# CLK_16GHz.net
KiCad netlist of a schematic drawn in Altium Designer
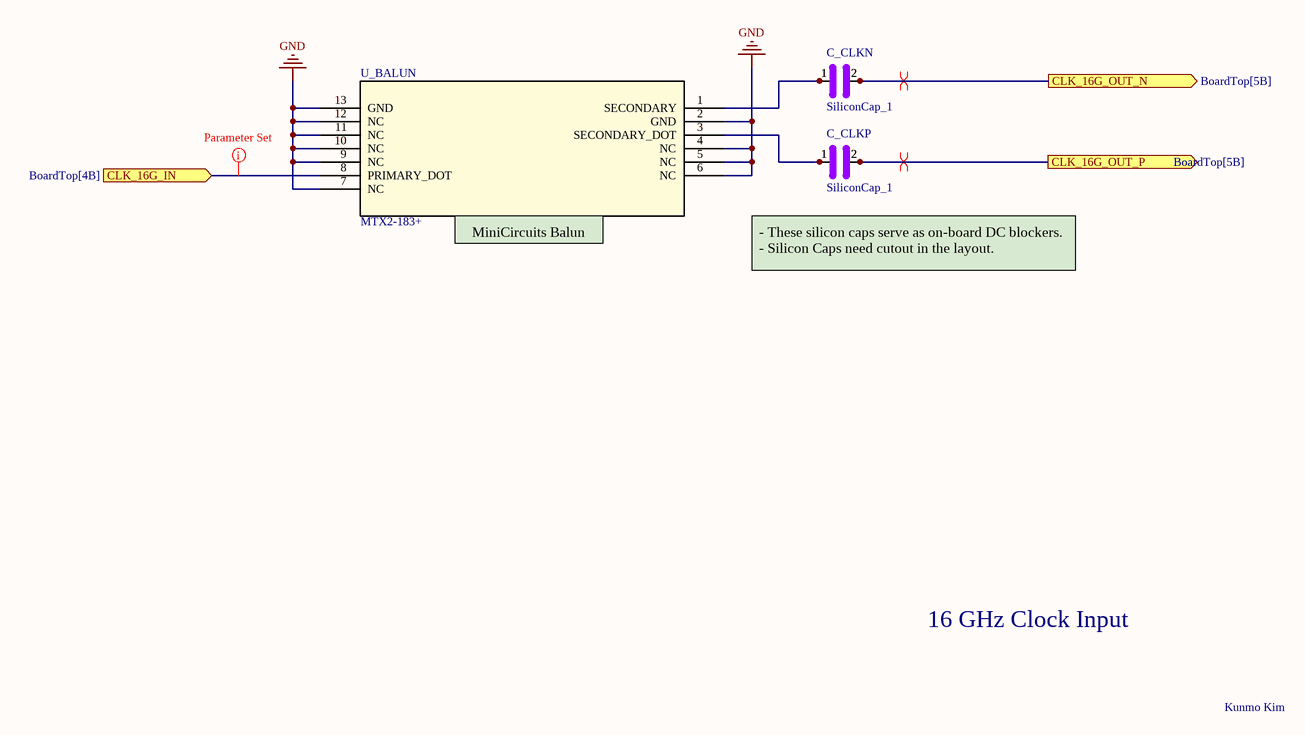
[diagram p0: CLK_16GHz.SchDoc]

(export (version "E")
  (design (tool "Eeschema 10.0.6"))
  (components
    (comp (ref "C_CLKN")
      (value "SiliconCap_1")
      (footprint "0201-NOSILK")
      (description "939114492510-T3S from Murata")
      (libsource (lib "DC_Blocker") (part "SiliconCap_1"))
    )
    (comp (ref "C_CLKP")
      (value "SiliconCap_1")
      (footprint "0201-NOSILK")
      (description "939114492510-T3S from Murata")
      (libsource (lib "DC_Blocker") (part "SiliconCap_1"))
    )
    (comp (ref "U_BALUN")
      (value "MTX2-183+")
      (footprint "DG3006_MNC")
      (libsource (lib "MTX2-133&plus_") (part "MTX2-133+"))
    )
  )
  (nets
    (net (code "1") (name "/CLK_16G_IN") (class "Default")
      (node (ref "U_BALUN") (pin "8") (pinfunction "PRIMARY_DOT_8") (pintype "passive"))
    )
    (net (code "2") (name "/CLK_16G_OUT_N") (class "Default")
      (node (ref "C_CLKN") (pin "2") (pinfunction "2_2") (pintype "passive"))
    )
    (net (code "3") (name "/CLK_16G_OUT_P") (class "Default")
      (node (ref "C_CLKP") (pin "2") (pinfunction "2_2") (pintype "passive"))
    )
    (net (code "4") (name "GND") (class "Default")
      (node (ref "U_BALUN") (pin "10") (pinfunction "NC_10") (pintype "passive"))
      (node (ref "U_BALUN") (pin "11") (pinfunction "NC_11") (pintype "passive"))
      (node (ref "U_BALUN") (pin "12") (pinfunction "NC_12") (pintype "passive"))
      (node (ref "U_BALUN") (pin "13") (pinfunction "GND_13") (pintype "power_in"))
      (node (ref "U_BALUN") (pin "2") (pinfunction "GND_2") (pintype "power_in"))
      (node (ref "U_BALUN") (pin "4") (pinfunction "NC_4") (pintype "passive"))
      (node (ref "U_BALUN") (pin "5") (pinfunction "NC_5") (pintype "passive"))
      (node (ref "U_BALUN") (pin "6") (pinfunction "NC_6") (pintype "passive"))
      (node (ref "U_BALUN") (pin "7") (pinfunction "NC_7") (pintype "passive"))
      (node (ref "U_BALUN") (pin "9") (pinfunction "NC_9") (pintype "passive"))
    )
    (net (code "5") (name "Net-(U_BALUN-SECONDARY)") (class "Default")
      (node (ref "C_CLKN") (pin "1") (pinfunction "1_1") (pintype "passive"))
      (node (ref "U_BALUN") (pin "1") (pinfunction "SECONDARY_1") (pintype "passive"))
    )
    (net (code "6") (name "Net-(U_BALUN-SECONDARY_DOT)") (class "Default")
      (node (ref "C_CLKP") (pin "1") (pinfunction "1_1") (pintype "passive"))
      (node (ref "U_BALUN") (pin "3") (pinfunction "SECONDARY_DOT_3") (pintype "passive"))
    )
  )
)
